# Power_Monitoring_Schematic.net
KiCad netlist of a schematic drawn in EAGLE
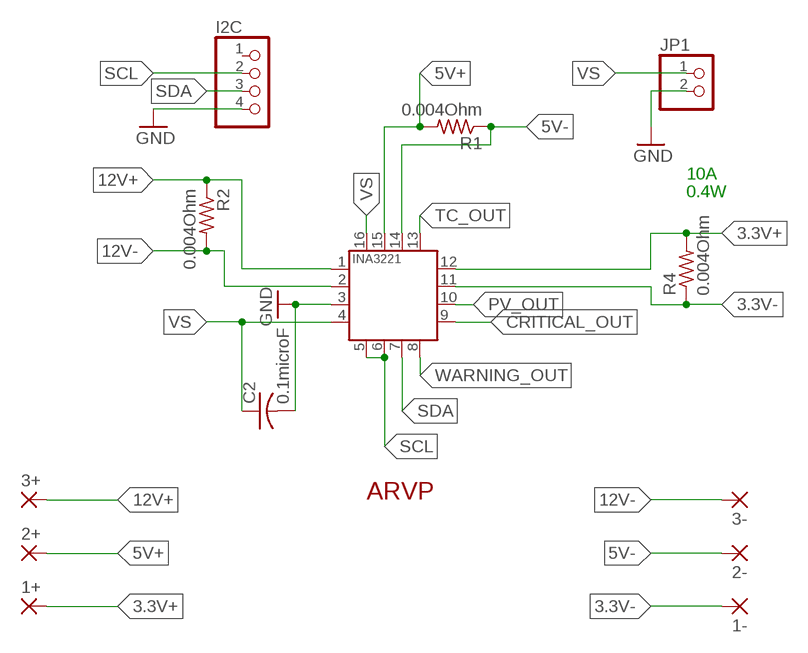
[diagram p0: schematic, sheet 1]

(export (version "E")
  (design (tool "Eeschema 10.0.6"))
  (components
    (comp (ref "1+")
      (value "3,81/1,5A")
      (footprint "eagle-import:3,81_1,5")
      (libsource (lib "eagle-import") (part "3,81/1,5A"))
    )
    (comp (ref "1-")
      (value "3,81/1,5A")
      (footprint "eagle-import:3,81_1,5")
      (libsource (lib "eagle-import") (part "3,81/1,5A"))
    )
    (comp (ref "2+")
      (value "3,81/1,5A")
      (footprint "eagle-import:3,81_1,5")
      (libsource (lib "eagle-import") (part "3,81/1,5A"))
    )
    (comp (ref "2-")
      (value "3,81/1,5A")
      (footprint "eagle-import:3,81_1,5")
      (libsource (lib "eagle-import") (part "3,81/1,5A"))
    )
    (comp (ref "3+")
      (value "3,81/1,5A")
      (footprint "eagle-import:3,81_1,5")
      (libsource (lib "eagle-import") (part "3,81/1,5A"))
    )
    (comp (ref "3-")
      (value "3,81/1,5A")
      (footprint "eagle-import:3,81_1,5")
      (libsource (lib "eagle-import") (part "3,81/1,5A"))
    )
    (comp (ref "ARVP1")
      (value "ARVP_LOGO")
      (footprint "eagle-import:ARVP")
      (libsource (lib "eagle-import") (part "ARVP_LOGO"))
    )
    (comp (ref "C2")
      (value "0.1microF")
      (footprint "eagle-import:C2012")
      (libsource (lib "eagle-import") (part "C-USC2012"))
    )
    (comp (ref "I2C")
      (value "PINHD-1X4")
      (footprint "eagle-import:1X04")
      (libsource (lib "eagle-import") (part "PINHD-1X4"))
    )
    (comp (ref "JP1")
      (value "PINHD-1X2")
      (footprint "eagle-import:1X02")
      (libsource (lib "eagle-import") (part "PINHD-1X2"))
    )
    (comp (ref "R1")
      (value "0.004Ohm")
      (footprint "eagle-import:R1206")
      (libsource (lib "eagle-import") (part "R-US_R1206"))
    )
    (comp (ref "R2")
      (value "0.004Ohm")
      (footprint "eagle-import:R1206")
      (libsource (lib "eagle-import") (part "R-US_R1206"))
    )
    (comp (ref "R4")
      (value "0.004Ohm")
      (footprint "eagle-import:R1206")
      (libsource (lib "eagle-import") (part "R-US_R1206"))
    )
    (comp (ref "U1")
      (value "INA3221.")
      (footprint "eagle-import:HVQFN16_4X4")
      (libsource (lib "eagle-import") (part "INA3221."))
    )
  )
  (nets
    (net (code "1") (name "3.3V+") (class "Default")
      (node (ref "1+") (pin "1") (pinfunction "P_1") (pintype "passive"))
      (node (ref "R4") (pin "2") (pinfunction "2_2") (pintype "passive"))
      (node (ref "U1") (pin "12") (pinfunction "IN+1_12") (pintype "input"))
    )
    (net (code "2") (name "3.3V-") (class "Default")
      (node (ref "1-") (pin "1") (pinfunction "P_1") (pintype "passive"))
      (node (ref "R4") (pin "1") (pinfunction "1_1") (pintype "passive"))
      (node (ref "U1") (pin "11") (pinfunction "IN-1_11") (pintype "input"))
    )
    (net (code "3") (name "5V+") (class "Default")
      (node (ref "2+") (pin "1") (pinfunction "P_1") (pintype "passive"))
      (node (ref "R1") (pin "2") (pinfunction "2_2") (pintype "passive"))
      (node (ref "U1") (pin "15") (pinfunction "IN+2_15") (pintype "input"))
    )
    (net (code "4") (name "5V-") (class "Default")
      (node (ref "2-") (pin "1") (pinfunction "P_1") (pintype "passive"))
      (node (ref "R1") (pin "1") (pinfunction "1_1") (pintype "passive"))
      (node (ref "U1") (pin "14") (pinfunction "IN-2_14") (pintype "input"))
    )
    (net (code "5") (name "12V+") (class "Default")
      (node (ref "3+") (pin "1") (pinfunction "P_1") (pintype "passive"))
      (node (ref "R2") (pin "1") (pinfunction "1_1") (pintype "passive"))
      (node (ref "U1") (pin "1") (pinfunction "IN-3_1") (pintype "input"))
    )
    (net (code "6") (name "12V-") (class "Default")
      (node (ref "3-") (pin "1") (pinfunction "P_1") (pintype "passive"))
      (node (ref "R2") (pin "2") (pinfunction "2_2") (pintype "passive"))
      (node (ref "U1") (pin "2") (pinfunction "IN+3_2") (pintype "input"))
    )
    (net (code "7") (name "CRITICAL_OUT") (class "Default")
      (node (ref "U1") (pin "9") (pinfunction "CRITICAL_9") (pintype "output"))
    )
    (net (code "8") (name "GND") (class "Default")
      (node (ref "C2") (pin "2") (pinfunction "2_2") (pintype "passive"))
      (node (ref "I2C") (pin "4") (pinfunction "4_4") (pintype "passive"))
      (node (ref "JP1") (pin "2") (pinfunction "2_2") (pintype "passive"))
      (node (ref "U1") (pin "3") (pinfunction "GND_3") (pintype "power_in"))
    )
    (net (code "9") (name "PV_OUT") (class "Default")
      (node (ref "U1") (pin "10") (pinfunction "PV_10") (pintype "output"))
    )
    (net (code "10") (name "SCL") (class "Default")
      (node (ref "I2C") (pin "2") (pinfunction "2_2") (pintype "passive"))
      (node (ref "U1") (pin "5") (pinfunction "A0_5") (pintype "input"))
      (node (ref "U1") (pin "6") (pinfunction "SCL_6") (pintype "input"))
    )
    (net (code "11") (name "SDA") (class "Default")
      (node (ref "I2C") (pin "3") (pinfunction "3_3") (pintype "passive"))
      (node (ref "U1") (pin "7") (pinfunction "SDA_7") (pintype "bidirectional"))
    )
    (net (code "12") (name "TC_OUT") (class "Default")
      (node (ref "U1") (pin "13") (pinfunction "TC_13") (pintype "output"))
    )
    (net (code "13") (name "VS") (class "Default")
      (node (ref "C2") (pin "1") (pinfunction "1_1") (pintype "passive"))
      (node (ref "JP1") (pin "1") (pinfunction "1_1") (pintype "passive"))
      (node (ref "U1") (pin "16") (pinfunction "VPU_16") (pintype "input"))
      (node (ref "U1") (pin "4") (pinfunction "VS_4") (pintype "power_in"))
    )
    (net (code "14") (name "WARNING_OUT") (class "Default")
      (node (ref "U1") (pin "8") (pinfunction "WARNING_8") (pintype "output"))
    )
    (net (code "15") (name "unconnected-(I2C-Pad1)") (class "Default")
      (node (ref "I2C") (pin "1") (pinfunction "1_1") (pintype "passive"))
    )
  )
)
